# MCU_ESP32_S3.net
KiCad netlist of a schematic drawn in Altium Designer
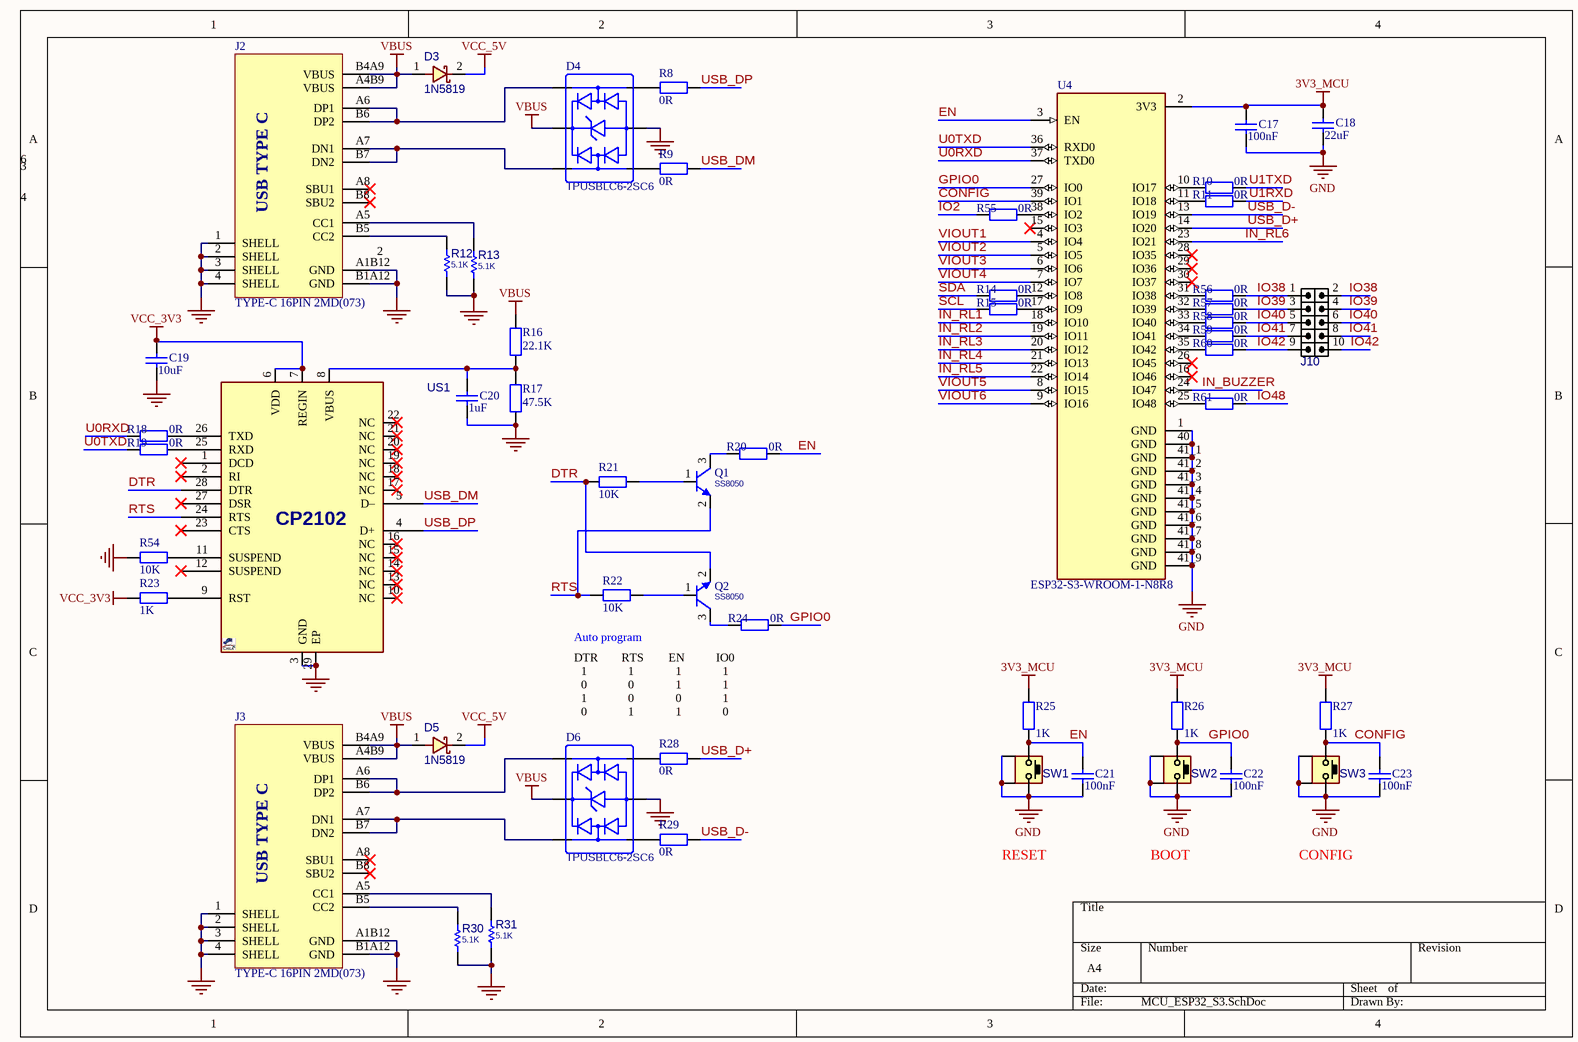
[diagram p0: MCU_ESP32_S3.SchDoc]

(export (version "E")
  (design (tool "Eeschema 10.0.6"))
  (components
    (comp (ref "C17")
      (value "100nF_0603_1%")
      (footprint "tu 0603")
      (description "Capacitor, Ceramic, 50V")
      (fields (field (name "MA_HANG") "100nF"))
      (libsource (lib "THU VIEN SCH") (part "Tu 0603 470pF 50V 10%"))
    )
    (comp (ref "C18")
      (value "22uF_0603_1%")
      (footprint "tu 0603")
      (description "Capacitor, Ceramic, 50V")
      (fields (field (name "MA_HANG") "22uF"))
      (libsource (lib "THU VIEN SCH") (part "Tu 0603 470pF 50V 10%"))
    )
    (comp (ref "C19")
      (value "10uF_0603_1%")
      (footprint "tu 0603")
      (description "Capacitor, Ceramic, 50V")
      (fields (field (name "MA_HANG") "10uF"))
      (libsource (lib "THU VIEN SCH") (part "Tu 0603 470pF 50V 10%"))
    )
    (comp (ref "C20")
      (value "1uF_0603_1%")
      (footprint "tu 0603")
      (description "Capacitor, Ceramic, 50V")
      (fields (field (name "MA_HANG") "1uF"))
      (libsource (lib "THU VIEN SCH") (part "Tu 0603 470pF 50V 10%"))
    )
    (comp (ref "C21")
      (value "100nF_0603_1%")
      (footprint "tu 0603")
      (description "Capacitor, Ceramic, 50V")
      (fields (field (name "MA_HANG") "100nF"))
      (libsource (lib "THU VIEN SCH") (part "Tu 0603 470pF 50V 10%"))
    )
    (comp (ref "C22")
      (value "100nF_0603_1%")
      (footprint "tu 0603")
      (description "Capacitor, Ceramic, 50V")
      (fields (field (name "MA_HANG") "100nF"))
      (libsource (lib "THU VIEN SCH") (part "Tu 0603 470pF 50V 10%"))
    )
    (comp (ref "C23")
      (value "100nF_0603_1%")
      (footprint "tu 0603")
      (description "Capacitor, Ceramic, 50V")
      (fields (field (name "MA_HANG") "100nF"))
      (libsource (lib "THU VIEN SCH") (part "Tu 0603 470pF 50V 10%"))
    )
    (comp (ref "D3")
      (value "1N5819")
      (footprint "D_SOD123W")
      (description "DIODE, SCHOTTKY, 40V, 1A")
      (fields (field (name "MANF") "DIODES") (field (name "MANF_P#") "1N5819HW-7-F"))
      (libsource (lib "AH_Library") (part "DIODE_SMD_SCHOTTKY_1N5819"))
    )
    (comp (ref "D4")
      (value "TPUSBLC6-2SC6")
      (footprint "SOT-23-6_L2.9-W1.6-P0.95-LS2.8-BR")
      (description "ESD ROHS SOT23-6 DIODES")
      (fields (field (name "LCSC PART NUMBER") "C558442") (field (name "MANUFACTURER") "TECH PUBLIC"))
      (libsource (lib "ESP32 S3 Gateway") (part "ESD_TPUSBLC6-2SC6"))
    )
    (comp (ref "D5")
      (value "1N5819")
      (footprint "D_SOD123W")
      (description "DIODE, SCHOTTKY, 40V, 1A")
      (fields (field (name "MANF") "DIODES") (field (name "MANF_P#") "1N5819HW-7-F"))
      (libsource (lib "AH_Library") (part "DIODE_SMD_SCHOTTKY_1N5819"))
    )
    (comp (ref "D6")
      (value "TPUSBLC6-2SC6")
      (footprint "SOT-23-6_L2.9-W1.6-P0.95-LS2.8-BR")
      (description "ESD ROHS SOT23-6 DIODES")
      (fields (field (name "LCSC PART NUMBER") "C558442") (field (name "MANUFACTURER") "TECH PUBLIC"))
      (libsource (lib "ESP32 S3 Gateway") (part "ESD_TPUSBLC6-2SC6"))
    )
    (comp (ref "J2")
      (value "TYPE-C 16PIN 2MD(073)")
      (footprint "USB-C-SMD_TYPE-C16PIN")
      (description "5A 1 Surface Mount 16 Female -25℃~+85℃ Type-C SMD USB Connectors ROHS")
      (fields
        (field (name "MANUFACTURER") "SHOU HAN")
        (field (name "MANUFACTURER PART NUMBER") "TYPE-C16PIN")
      )
      (libsource (lib "ESP32 S3 Gateway") (part "TYPE-C 16PIN 2MD(073)"))
    )
    (comp (ref "J3")
      (value "TYPE-C 16PIN 2MD(073)")
      (footprint "USB-C-SMD_TYPE-C16PIN")
      (description "5A 1 Surface Mount 16 Female -25℃~+85℃ Type-C SMD USB Connectors ROHS")
      (fields
        (field (name "MANUFACTURER") "SHOU HAN")
        (field (name "MANUFACTURER PART NUMBER") "TYPE-C16PIN")
      )
      (libsource (lib "ESP32 S3 Gateway") (part "TYPE-C 16PIN 2MD(073)"))
    )
    (comp (ref "J10")
      (value "HDRMINI_2X5")
      (footprint "HDRMINI_M_2X5")
      (description "CONN, HEADER, Male, pitch: 1.27mm, 10POS")
      (libsource (lib "AH_Library") (part "HDRMINI_M_2X5"))
    )
    (comp (ref "Q1")
      (value "SS8050")
      (footprint "SOT23_3")
      (description "BJT, NPN, 25v, 1.5A, SMD, SOT23")
      (fields (field (name "MANF_P#") "MMBT8050") (field (name "MANF") "GALAXY"))
      (libsource (lib "AH_Library") (part "NPN_MMBT8050_SOT23"))
    )
    (comp (ref "Q2")
      (value "SS8050")
      (footprint "SOT23_3")
      (description "BJT, NPN, 25v, 1.5A, SMD, SOT23")
      (fields (field (name "MANF_P#") "MMBT8050") (field (name "MANF") "GALAXY"))
      (libsource (lib "AH_Library") (part "NPN_MMBT8050_SOT23"))
    )
    (comp (ref "R8")
      (value "0R_0603_1%")
      (footprint "tro smd 0603")
      (description "RES SMD 0603")
      (fields (field (name "MA_HANG") "0R"))
      (libsource (lib "THU VIEN SCH") (part "Tro 0603 5% 10k"))
    )
    (comp (ref "R9")
      (value "0R_0603_1%")
      (footprint "tro smd 0603")
      (description "RES SMD 0603")
      (fields (field (name "MA_HANG") "0R"))
      (libsource (lib "THU VIEN SCH") (part "Tro 0603 5% 10k"))
    )
    (comp (ref "R10")
      (value "0R_0603_1%")
      (footprint "tro smd 0603")
      (description "RES SMD 0603")
      (fields (field (name "MA_HANG") "0R"))
      (libsource (lib "THU VIEN SCH") (part "Tro 0603 5% 10k"))
    )
    (comp (ref "R11")
      (value "0R_0603_1%")
      (footprint "tro smd 0603")
      (description "RES SMD 0603")
      (fields (field (name "MA_HANG") "0R"))
      (libsource (lib "THU VIEN SCH") (part "Tro 0603 5% 10k"))
    )
    (comp (ref "R12")
      (value "5.1K")
      (footprint "R0603")
      (description "RESISTOR, SMD")
      (fields (field (name "Comment") "5K1_0603_1%"))
      (libsource (lib "AH_Library") (part "RES_SMD_0603"))
    )
    (comp (ref "R13")
      (value "5.1K")
      (footprint "R0603")
      (description "RESISTOR, SMD")
      (fields (field (name "Comment") "5K1_0603_1%"))
      (libsource (lib "AH_Library") (part "RES_SMD_0603"))
    )
    (comp (ref "R14")
      (value "0R_0603_1%")
      (footprint "tro smd 0603")
      (description "RES SMD 0603")
      (fields (field (name "MA_HANG") "0R"))
      (libsource (lib "THU VIEN SCH") (part "Tro 0603 5% 10k"))
    )
    (comp (ref "R15")
      (value "0R_0603_1%")
      (footprint "tro smd 0603")
      (description "RES SMD 0603")
      (fields (field (name "MA_HANG") "0R"))
      (libsource (lib "THU VIEN SCH") (part "Tro 0603 5% 10k"))
    )
    (comp (ref "R16")
      (value "22.1K_0603_1%")
      (footprint "tro smd 0603")
      (description "RES SMD 0603")
      (fields (field (name "MA_HANG") "22.1K"))
      (libsource (lib "THU VIEN SCH") (part "Tro 0603 5% 10k"))
    )
    (comp (ref "R17")
      (value "47.5K_0603_1%")
      (footprint "tro smd 0603")
      (description "RES SMD 0603")
      (fields (field (name "MA_HANG") "47.5K"))
      (libsource (lib "THU VIEN SCH") (part "Tro 0603 5% 10k"))
    )
    (comp (ref "R18")
      (value "0R_0603_1%")
      (footprint "tro smd 0603")
      (description "RES SMD 0603")
      (fields (field (name "MA_HANG") "0R"))
      (libsource (lib "THU VIEN SCH") (part "Tro 0603 5% 10k"))
    )
    (comp (ref "R19")
      (value "0R_0603_1%")
      (footprint "tro smd 0603")
      (description "RES SMD 0603")
      (fields (field (name "MA_HANG") "0R"))
      (libsource (lib "THU VIEN SCH") (part "Tro 0603 5% 10k"))
    )
    (comp (ref "R20")
      (value "0R_0603_1%")
      (footprint "tro smd 0603")
      (description "RES SMD 0603")
      (fields (field (name "MA_HANG") "0R"))
      (libsource (lib "THU VIEN SCH") (part "Tro 0603 5% 10k"))
    )
    (comp (ref "R21")
      (value "10K_0603_1%")
      (footprint "tro smd 0603")
      (description "RES SMD 0603")
      (fields (field (name "MA_HANG") "10K"))
      (libsource (lib "THU VIEN SCH") (part "Tro 0603 5% 10k"))
    )
    (comp (ref "R22")
      (value "10K_0603_1%")
      (footprint "tro smd 0603")
      (description "RES SMD 0603")
      (fields (field (name "MA_HANG") "10K"))
      (libsource (lib "THU VIEN SCH") (part "Tro 0603 5% 10k"))
    )
    (comp (ref "R23")
      (value "1K_0603_1%")
      (footprint "tro smd 0603")
      (description "RES SMD 0603")
      (fields (field (name "MA_HANG") "1K"))
      (libsource (lib "THU VIEN SCH") (part "Tro 0603 5% 10k"))
    )
    (comp (ref "R24")
      (value "0R_0603_1%")
      (footprint "tro smd 0603")
      (description "RES SMD 0603")
      (fields (field (name "MA_HANG") "0R"))
      (libsource (lib "THU VIEN SCH") (part "Tro 0603 5% 10k"))
    )
    (comp (ref "R25")
      (value "1K_0603_1%")
      (footprint "tro smd 0603")
      (description "RES SMD 0603")
      (fields (field (name "MA_HANG") "1K"))
      (libsource (lib "THU VIEN SCH") (part "Tro 0603 5% 10k"))
    )
    (comp (ref "R26")
      (value "1K_0603_1%")
      (footprint "tro smd 0603")
      (description "RES SMD 0603")
      (fields (field (name "MA_HANG") "1K"))
      (libsource (lib "THU VIEN SCH") (part "Tro 0603 5% 10k"))
    )
    (comp (ref "R27")
      (value "1K_0603_1%")
      (footprint "tro smd 0603")
      (description "RES SMD 0603")
      (fields (field (name "MA_HANG") "1K"))
      (libsource (lib "THU VIEN SCH") (part "Tro 0603 5% 10k"))
    )
    (comp (ref "R28")
      (value "0R_0603_1%")
      (footprint "tro smd 0603")
      (description "RES SMD 0603")
      (fields (field (name "MA_HANG") "0R"))
      (libsource (lib "THU VIEN SCH") (part "Tro 0603 5% 10k"))
    )
    (comp (ref "R29")
      (value "0R_0603_1%")
      (footprint "tro smd 0603")
      (description "RES SMD 0603")
      (fields (field (name "MA_HANG") "0R"))
      (libsource (lib "THU VIEN SCH") (part "Tro 0603 5% 10k"))
    )
    (comp (ref "R30")
      (value "5.1K")
      (footprint "R0603")
      (description "RESISTOR, SMD")
      (fields (field (name "Comment") "5K1_0603_1%"))
      (libsource (lib "AH_Library") (part "RES_SMD_0603"))
    )
    (comp (ref "R31")
      (value "5.1K")
      (footprint "R0603")
      (description "RESISTOR, SMD")
      (fields (field (name "Comment") "5K1_0603_1%"))
      (libsource (lib "AH_Library") (part "RES_SMD_0603"))
    )
    (comp (ref "R54")
      (value "10K_0603_1%")
      (footprint "tro smd 0603")
      (description "RES SMD 0603")
      (fields (field (name "MA_HANG") "10K"))
      (libsource (lib "THU VIEN SCH") (part "Tro 0603 5% 10k"))
    )
    (comp (ref "R55")
      (value "0R_0603_1%")
      (footprint "tro smd 0603")
      (description "RES SMD 0603")
      (fields (field (name "MA_HANG") "0R"))
      (libsource (lib "THU VIEN SCH") (part "Tro 0603 5% 10k"))
    )
    (comp (ref "R56")
      (value "0R_0603_1%")
      (footprint "tro smd 0603")
      (description "RES SMD 0603")
      (fields (field (name "MA_HANG") "0R"))
      (libsource (lib "THU VIEN SCH") (part "Tro 0603 5% 10k"))
    )
    (comp (ref "R57")
      (value "0R_0603_1%")
      (footprint "tro smd 0603")
      (description "RES SMD 0603")
      (fields (field (name "MA_HANG") "0R"))
      (libsource (lib "THU VIEN SCH") (part "Tro 0603 5% 10k"))
    )
    (comp (ref "R58")
      (value "0R_0603_1%")
      (footprint "tro smd 0603")
      (description "RES SMD 0603")
      (fields (field (name "MA_HANG") "0R"))
      (libsource (lib "THU VIEN SCH") (part "Tro 0603 5% 10k"))
    )
    (comp (ref "R59")
      (value "0R_0603_1%")
      (footprint "tro smd 0603")
      (description "RES SMD 0603")
      (fields (field (name "MA_HANG") "0R"))
      (libsource (lib "THU VIEN SCH") (part "Tro 0603 5% 10k"))
    )
    (comp (ref "R60")
      (value "0R_0603_1%")
      (footprint "tro smd 0603")
      (description "RES SMD 0603")
      (fields (field (name "MA_HANG") "0R"))
      (libsource (lib "THU VIEN SCH") (part "Tro 0603 5% 10k"))
    )
    (comp (ref "R61")
      (value "0R_0603_1%")
      (footprint "tro smd 0603")
      (description "RES SMD 0603")
      (fields (field (name "MA_HANG") "0R"))
      (libsource (lib "THU VIEN SCH") (part "Tro 0603 5% 10k"))
    )
    (comp (ref "SW1")
      (value "PUSHBUTTON")
      (footprint "SWPBT_SPST_R_6X6X10")
      (description "SWITCH, PUSH BUTTON, TACTILE, THD, SPST, RIGHT")
      (libsource (lib "AH_Library") (part "SWPBT_SPST_R_6X6X10"))
    )
    (comp (ref "SW2")
      (value "PUSHBUTTON")
      (footprint "SWPBT_SPST_R_6X6X10")
      (description "SWITCH, PUSH BUTTON, TACTILE, THD, SPST, RIGHT")
      (libsource (lib "AH_Library") (part "SWPBT_SPST_R_6X6X10"))
    )
    (comp (ref "SW3")
      (value "PUSHBUTTON")
      (footprint "SWPBT_SPST_R_6X6X10")
      (description "SWITCH, PUSH BUTTON, TACTILE, THD, SPST, RIGHT")
      (libsource (lib "AH_Library") (part "SWPBT_SPST_R_6X6X10"))
    )
    (comp (ref "U4")
      (value "ESP32-S3-WROOM-1-N8R8")
      (footprint "XCVR_ESP32S3WROOM1N8R8")
      (description "Bluetooth, WiFi 802.11b/g/n, Bluetooth v5.0 Transceiver Module 2.4GHz PCB Trace Surface Mount")
      (fields (field (name "MF") "Espressif Systems"))
      (libsource (lib "ESP32-S3-WROOM-1-N8R8") (part "ESP32-S3-WROOM-1-N8R8"))
    )
    (comp (ref "US1")
      (value "CP2102_QFN28")
      (footprint "QFN50_28T")
      (description "USB-UART BRIDGE")
      (fields (field (name "MANF") "SILICON LABS") (field (name "MANF_1") "MANF"))
      (libsource (lib "AH_Library") (part "CP2102_QFN28"))
    )
  )
  (nets
    (net (code "1") (name "/CONFIG") (class "Default")
      (node (ref "C23") (pin "1") (pinfunction "1_1") (pintype "passive"))
      (node (ref "R27") (pin "1") (pinfunction "1_1") (pintype "passive"))
      (node (ref "SW3") (pin "1") (pinfunction "1_1") (pintype "passive"))
      (node (ref "U4") (pin "39") (pinfunction "IO1_39") (pintype "bidirectional"))
    )
    (net (code "2") (name "/DTR") (class "Default")
      (node (ref "Q2") (pin "2") (pinfunction "E_2") (pintype "passive"))
      (node (ref "R21") (pin "2") (pinfunction "2_2") (pintype "passive"))
      (node (ref "US1") (pin "28") (pinfunction "DTR_28") (pintype "passive"))
    )
    (net (code "3") (name "/EN") (class "Default")
      (node (ref "C21") (pin "1") (pinfunction "1_1") (pintype "passive"))
      (node (ref "R20") (pin "2") (pinfunction "2_2") (pintype "passive"))
      (node (ref "R25") (pin "1") (pinfunction "1_1") (pintype "passive"))
      (node (ref "SW1") (pin "1") (pinfunction "1_1") (pintype "passive"))
      (node (ref "U4") (pin "3") (pinfunction "EN_3") (pintype "input"))
    )
    (net (code "4") (name "/GPIO0") (class "Default")
      (node (ref "C22") (pin "1") (pinfunction "1_1") (pintype "passive"))
      (node (ref "R24") (pin "2") (pinfunction "2_2") (pintype "passive"))
      (node (ref "R26") (pin "1") (pinfunction "1_1") (pintype "passive"))
      (node (ref "SW2") (pin "1") (pinfunction "1_1") (pintype "passive"))
      (node (ref "U4") (pin "27") (pinfunction "IO0_27") (pintype "bidirectional"))
    )
    (net (code "5") (name "/IN_BUZZER") (class "Default")
      (node (ref "U4") (pin "24") (pinfunction "IO47_24") (pintype "bidirectional"))
    )
    (net (code "6") (name "/IN_RL1") (class "Default")
      (node (ref "U4") (pin "18") (pinfunction "IO10_18") (pintype "bidirectional"))
    )
    (net (code "7") (name "/IN_RL2") (class "Default")
      (node (ref "U4") (pin "19") (pinfunction "IO11_19") (pintype "bidirectional"))
    )
    (net (code "8") (name "/IN_RL3") (class "Default")
      (node (ref "U4") (pin "20") (pinfunction "IO12_20") (pintype "bidirectional"))
    )
    (net (code "9") (name "/IN_RL4") (class "Default")
      (node (ref "U4") (pin "21") (pinfunction "IO13_21") (pintype "bidirectional"))
    )
    (net (code "10") (name "/IN_RL5") (class "Default")
      (node (ref "U4") (pin "22") (pinfunction "IO14_22") (pintype "bidirectional"))
    )
    (net (code "11") (name "/IN_RL6") (class "Default")
      (node (ref "U4") (pin "23") (pinfunction "IO21_23") (pintype "bidirectional"))
    )
    (net (code "12") (name "/IO2") (class "Default")
      (node (ref "R55") (pin "1") (pinfunction "1_1") (pintype "passive"))
    )
    (net (code "13") (name "/IO38") (class "Default")
      (node (ref "J10") (pin "1") (pinfunction "1_1") (pintype "passive"))
      (node (ref "J10") (pin "2") (pinfunction "2_2") (pintype "passive"))
      (node (ref "R56") (pin "2") (pinfunction "2_2") (pintype "passive"))
    )
    (net (code "14") (name "/IO39") (class "Default")
      (node (ref "J10") (pin "3") (pinfunction "3_3") (pintype "passive"))
      (node (ref "J10") (pin "4") (pinfunction "4_4") (pintype "passive"))
      (node (ref "R57") (pin "2") (pinfunction "2_2") (pintype "passive"))
    )
    (net (code "15") (name "/IO40") (class "Default")
      (node (ref "J10") (pin "5") (pinfunction "5_5") (pintype "passive"))
      (node (ref "J10") (pin "6") (pinfunction "6_6") (pintype "passive"))
      (node (ref "R58") (pin "2") (pinfunction "2_2") (pintype "passive"))
    )
    (net (code "16") (name "/IO41") (class "Default")
      (node (ref "J10") (pin "7") (pinfunction "7_7") (pintype "passive"))
      (node (ref "J10") (pin "8") (pinfunction "8_8") (pintype "passive"))
      (node (ref "R59") (pin "2") (pinfunction "2_2") (pintype "passive"))
    )
    (net (code "17") (name "/IO42") (class "Default")
      (node (ref "J10") (pin "10") (pinfunction "10_10") (pintype "passive"))
      (node (ref "J10") (pin "9") (pinfunction "9_9") (pintype "passive"))
      (node (ref "R60") (pin "2") (pinfunction "2_2") (pintype "passive"))
    )
    (net (code "18") (name "/IO48") (class "Default")
      (node (ref "R61") (pin "2") (pinfunction "2_2") (pintype "passive"))
    )
    (net (code "19") (name "/RTS") (class "Default")
      (node (ref "Q1") (pin "2") (pinfunction "E_2") (pintype "passive"))
      (node (ref "R22") (pin "2") (pinfunction "2_2") (pintype "passive"))
      (node (ref "US1") (pin "24") (pinfunction "RTS_24") (pintype "passive"))
    )
    (net (code "20") (name "/SCL") (class "Default")
      (node (ref "R15") (pin "1") (pinfunction "1_1") (pintype "passive"))
    )
    (net (code "21") (name "/SDA") (class "Default")
      (node (ref "R14") (pin "1") (pinfunction "1_1") (pintype "passive"))
    )
    (net (code "22") (name "/U0RXD") (class "Default")
      (node (ref "R18") (pin "1") (pinfunction "1_1") (pintype "passive"))
      (node (ref "U4") (pin "37") (pinfunction "TXD0_37") (pintype "bidirectional"))
    )
    (net (code "23") (name "/U0TXD") (class "Default")
      (node (ref "R19") (pin "1") (pinfunction "1_1") (pintype "passive"))
      (node (ref "U4") (pin "36") (pinfunction "RXD0_36") (pintype "bidirectional"))
    )
    (net (code "24") (name "/U1RXD") (class "Default")
      (node (ref "R11") (pin "2") (pinfunction "2_2") (pintype "passive"))
    )
    (net (code "25") (name "/U1TXD") (class "Default")
      (node (ref "R10") (pin "2") (pinfunction "2_2") (pintype "passive"))
    )
    (net (code "26") (name "/USB_D+") (class "Default")
      (node (ref "R28") (pin "2") (pinfunction "2_2") (pintype "passive"))
      (node (ref "U4") (pin "14") (pinfunction "IO20_14") (pintype "bidirectional"))
    )
    (net (code "27") (name "/USB_D-") (class "Default")
      (node (ref "R29") (pin "2") (pinfunction "2_2") (pintype "passive"))
      (node (ref "U4") (pin "13") (pinfunction "IO19_13") (pintype "bidirectional"))
    )
    (net (code "28") (name "/USB_DM") (class "Default")
      (node (ref "R9") (pin "2") (pinfunction "2_2") (pintype "passive"))
      (node (ref "US1") (pin "5") (pinfunction "D–_5") (pintype "passive"))
    )
    (net (code "29") (name "/USB_DP") (class "Default")
      (node (ref "R8") (pin "2") (pinfunction "2_2") (pintype "passive"))
      (node (ref "US1") (pin "4") (pinfunction "D+_4") (pintype "passive"))
    )
    (net (code "30") (name "/VIOUT1") (class "Default")
      (node (ref "U4") (pin "4") (pinfunction "IO4_4") (pintype "bidirectional"))
    )
    (net (code "31") (name "/VIOUT2") (class "Default")
      (node (ref "U4") (pin "5") (pinfunction "IO5_5") (pintype "bidirectional"))
    )
    (net (code "32") (name "/VIOUT3") (class "Default")
      (node (ref "U4") (pin "6") (pinfunction "IO6_6") (pintype "bidirectional"))
    )
    (net (code "33") (name "/VIOUT4") (class "Default")
      (node (ref "U4") (pin "7") (pinfunction "IO7_7") (pintype "bidirectional"))
    )
    (net (code "34") (name "/VIOUT5") (class "Default")
      (node (ref "U4") (pin "8") (pinfunction "IO15_8") (pintype "bidirectional"))
    )
    (net (code "35") (name "/VIOUT6") (class "Default")
      (node (ref "U4") (pin "9") (pinfunction "IO16_9") (pintype "bidirectional"))
    )
    (net (code "36") (name "3V3_MCU") (class "Default")
      (node (ref "C17") (pin "1") (pinfunction "1_1") (pintype "passive"))
      (node (ref "C18") (pin "1") (pinfunction "1_1") (pintype "passive"))
      (node (ref "R25") (pin "2") (pinfunction "2_2") (pintype "passive"))
      (node (ref "R26") (pin "2") (pinfunction "2_2") (pintype "passive"))
      (node (ref "R27") (pin "2") (pinfunction "2_2") (pintype "passive"))
      (node (ref "U4") (pin "2") (pinfunction "3V3_2") (pintype "power_in"))
    )
    (net (code "37") (name "GND") (class "Default")
      (node (ref "C17") (pin "2") (pinfunction "2_2") (pintype "passive"))
      (node (ref "C18") (pin "2") (pinfunction "2_2") (pintype "passive"))
      (node (ref "C19") (pin "2") (pinfunction "2_2") (pintype "passive"))
      (node (ref "C20") (pin "2") (pinfunction "2_2") (pintype "passive"))
      (node (ref "C21") (pin "2") (pinfunction "2_2") (pintype "passive"))
      (node (ref "C22") (pin "2") (pinfunction "2_2") (pintype "passive"))
      (node (ref "C23") (pin "2") (pinfunction "2_2") (pintype "passive"))
      (node (ref "D4") (pin "2") (pinfunction "GND_2") (pintype "passive"))
      (node (ref "D6") (pin "2") (pinfunction "GND_2") (pintype "passive"))
      (node (ref "J2") (pin "1") (pinfunction "SHELL_1") (pintype "passive"))
      (node (ref "J2") (pin "2") (pinfunction "SHELL_2") (pintype "passive"))
      (node (ref "J2") (pin "3") (pinfunction "SHELL_3") (pintype "passive"))
      (node (ref "J2") (pin "4") (pinfunction "SHELL_4") (pintype "passive"))
      (node (ref "J2") (pin "A1B12") (pinfunction "GND_A1B12") (pintype "passive"))
      (node (ref "J2") (pin "B1A12") (pinfunction "GND_B1A12") (pintype "passive"))
      (node (ref "J3") (pin "1") (pinfunction "SHELL_1") (pintype "passive"))
      (node (ref "J3") (pin "2") (pinfunction "SHELL_2") (pintype "passive"))
      (node (ref "J3") (pin "3") (pinfunction "SHELL_3") (pintype "passive"))
      (node (ref "J3") (pin "4") (pinfunction "SHELL_4") (pintype "passive"))
      (node (ref "J3") (pin "A1B12") (pinfunction "GND_A1B12") (pintype "passive"))
      (node (ref "J3") (pin "B1A12") (pinfunction "GND_B1A12") (pintype "passive"))
      (node (ref "R12") (pin "2") (pinfunction "2_2") (pintype "passive"))
      (node (ref "R13") (pin "2") (pinfunction "2_2") (pintype "passive"))
      (node (ref "R17") (pin "2") (pinfunction "2_2") (pintype "passive"))
      (node (ref "R30") (pin "2") (pinfunction "2_2") (pintype "passive"))
      (node (ref "R31") (pin "2") (pinfunction "2_2") (pintype "passive"))
      (node (ref "R54") (pin "2") (pinfunction "2_2") (pintype "passive"))
      (node (ref "SW1") (pin "2") (pinfunction "2_2") (pintype "passive"))
      (node (ref "SW1") (pin "MH1") (pinfunction "MH1_MH1") (pintype "passive"))
      (node (ref "SW1") (pin "MH2") (pinfunction "MH2_MH2") (pintype "passive"))
      (node (ref "SW2") (pin "2") (pinfunction "2_2") (pintype "passive"))
      (node (ref "SW2") (pin "MH1") (pinfunction "MH1_MH1") (pintype "passive"))
      (node (ref "SW2") (pin "MH2") (pinfunction "MH2_MH2") (pintype "passive"))
      (node (ref "SW3") (pin "2") (pinfunction "2_2") (pintype "passive"))
      (node (ref "SW3") (pin "MH1") (pinfunction "MH1_MH1") (pintype "passive"))
      (node (ref "SW3") (pin "MH2") (pinfunction "MH2_MH2") (pintype "passive"))
      (node (ref "U4") (pin "1") (pinfunction "GND_1") (pintype "power_in"))
      (node (ref "U4") (pin "40") (pinfunction "GND_40") (pintype "power_in"))
      (node (ref "U4") (pin "41_1") (pinfunction "GND_41_1") (pintype "power_in"))
      (node (ref "U4") (pin "41_2") (pinfunction "GND_41_2") (pintype "power_in"))
      (node (ref "U4") (pin "41_3") (pinfunction "GND_41_3") (pintype "power_in"))
      (node (ref "U4") (pin "41_4") (pinfunction "GND_41_4") (pintype "power_in"))
      (node (ref "U4") (pin "41_5") (pinfunction "GND_41_5") (pintype "power_in"))
      (node (ref "U4") (pin "41_6") (pinfunction "GND_41_6") (pintype "power_in"))
      (node (ref "U4") (pin "41_7") (pinfunction "GND_41_7") (pintype "power_in"))
      (node (ref "U4") (pin "41_8") (pinfunction "GND_41_8") (pintype "power_in"))
      (node (ref "U4") (pin "41_9") (pinfunction "GND_41_9") (pintype "power_in"))
      (node (ref "US1") (pin "29") (pinfunction "EP_29") (pintype "passive"))
      (node (ref "US1") (pin "3") (pinfunction "GND_3") (pintype "passive"))
    )
    (net (code "38") (name "Net-(D4-I{slash}O1-Pad1)") (class "Default")
      (node (ref "D4") (pin "1") (pinfunction "I/O1_1") (pintype "passive"))
      (node (ref "R8") (pin "1") (pinfunction "1_1") (pintype "passive"))
    )
    (net (code "39") (name "Net-(D4-I{slash}O2-Pad3)") (class "Default")
      (node (ref "D4") (pin "3") (pinfunction "I/O2_3") (pintype "passive"))
      (node (ref "R9") (pin "1") (pinfunction "1_1") (pintype "passive"))
    )
    (net (code "40") (name "Net-(D6-I{slash}O1-Pad1)") (class "Default")
      (node (ref "D6") (pin "1") (pinfunction "I/O1_1") (pintype "passive"))
      (node (ref "R28") (pin "1") (pinfunction "1_1") (pintype "passive"))
    )
    (net (code "41") (name "Net-(D6-I{slash}O2-Pad3)") (class "Default")
      (node (ref "D6") (pin "3") (pinfunction "I/O2_3") (pintype "passive"))
      (node (ref "R29") (pin "1") (pinfunction "1_1") (pintype "passive"))
    )
    (net (code "42") (name "Net-(J2-CC1)") (class "Default")
      (node (ref "J2") (pin "A5") (pinfunction "CC1_A5") (pintype "passive"))
      (node (ref "R13") (pin "1") (pinfunction "1_1") (pintype "passive"))
    )
    (net (code "43") (name "Net-(J2-CC2)") (class "Default")
      (node (ref "J2") (pin "B5") (pinfunction "CC2_B5") (pintype "passive"))
      (node (ref "R12") (pin "1") (pinfunction "1_1") (pintype "passive"))
    )
    (net (code "44") (name "Net-(J2-DN1)") (class "Default")
      (node (ref "D4") (pin "4") (pinfunction "I/O2_4") (pintype "passive"))
      (node (ref "J2") (pin "A7") (pinfunction "DN1_A7") (pintype "passive"))
      (node (ref "J2") (pin "B7") (pinfunction "DN2_B7") (pintype "passive"))
    )
    (net (code "45") (name "Net-(J2-DP1)") (class "Default")
      (node (ref "D4") (pin "6") (pinfunction "I/O1_6") (pintype "passive"))
      (node (ref "J2") (pin "A6") (pinfunction "DP1_A6") (pintype "passive"))
      (node (ref "J2") (pin "B6") (pinfunction "DP2_B6") (pintype "passive"))
    )
    (net (code "46") (name "Net-(J3-CC1)") (class "Default")
      (node (ref "J3") (pin "A5") (pinfunction "CC1_A5") (pintype "passive"))
      (node (ref "R31") (pin "1") (pinfunction "1_1") (pintype "passive"))
    )
    (net (code "47") (name "Net-(J3-CC2)") (class "Default")
      (node (ref "J3") (pin "B5") (pinfunction "CC2_B5") (pintype "passive"))
      (node (ref "R30") (pin "1") (pinfunction "1_1") (pintype "passive"))
    )
    (net (code "48") (name "Net-(J3-DN1)") (class "Default")
      (node (ref "D6") (pin "4") (pinfunction "I/O2_4") (pintype "passive"))
      (node (ref "J3") (pin "A7") (pinfunction "DN1_A7") (pintype "passive"))
      (node (ref "J3") (pin "B7") (pinfunction "DN2_B7") (pintype "passive"))
    )
    (net (code "49") (name "Net-(J3-DP1)") (class "Default")
      (node (ref "D6") (pin "6") (pinfunction "I/O1_6") (pintype "passive"))
      (node (ref "J3") (pin "A6") (pinfunction "DP1_A6") (pintype "passive"))
      (node (ref "J3") (pin "B6") (pinfunction "DP2_B6") (pintype "passive"))
    )
    (net (code "50") (name "Net-(Q1-B)") (class "Default")
      (node (ref "Q1") (pin "1") (pinfunction "B_1") (pintype "passive"))
      (node (ref "R21") (pin "1") (pinfunction "1_1") (pintype "passive"))
    )
    (net (code "51") (name "Net-(Q1-C)") (class "Default")
      (node (ref "Q1") (pin "3") (pinfunction "C_3") (pintype "passive"))
      (node (ref "R20") (pin "1") (pinfunction "1_1") (pintype "passive"))
    )
    (net (code "52") (name "Net-(Q2-B)") (class "Default")
      (node (ref "Q2") (pin "1") (pinfunction "B_1") (pintype "passive"))
      (node (ref "R22") (pin "1") (pinfunction "1_1") (pintype "passive"))
    )
    (net (code "53") (name "Net-(Q2-C)") (class "Default")
      (node (ref "Q2") (pin "3") (pinfunction "C_3") (pintype "passive"))
      (node (ref "R24") (pin "1") (pinfunction "1_1") (pintype "passive"))
    )
    (net (code "54") (name "Net-(R54-Pad1)") (class "Default")
      (node (ref "R54") (pin "1") (pinfunction "1_1") (pintype "passive"))
      (node (ref "US1") (pin "11") (pinfunction "SUSPEND_11") (pintype "passive"))
    )
    (net (code "55") (name "Net-(U4-IO2)") (class "Default")
      (node (ref "R55") (pin "2") (pinfunction "2_2") (pintype "passive"))
      (node (ref "U4") (pin "38") (pinfunction "IO2_38") (pintype "bidirectional"))
    )
    (net (code "56") (name "Net-(U4-IO8)") (class "Default")
      (node (ref "R14") (pin "2") (pinfunction "2_2") (pintype "passive"))
      (node (ref "U4") (pin "12") (pinfunction "IO8_12") (pintype "bidirectional"))
    )
    (net (code "57") (name "Net-(U4-IO9)") (class "Default")
      (node (ref "R15") (pin "2") (pinfunction "2_2") (pintype "passive"))
      (node (ref "U4") (pin "17") (pinfunction "IO9_17") (pintype "bidirectional"))
    )
    (net (code "58") (name "Net-(U4-IO17)") (class "Default")
      (node (ref "R10") (pin "1") (pinfunction "1_1") (pintype "passive"))
      (node (ref "U4") (pin "10") (pinfunction "IO17_10") (pintype "bidirectional"))
    )
    (net (code "59") (name "Net-(U4-IO18)") (class "Default")
      (node (ref "R11") (pin "1") (pinfunction "1_1") (pintype "passive"))
      (node (ref "U4") (pin "11") (pinfunction "IO18_11") (pintype "bidirectional"))
    )
    (net (code "60") (name "Net-(U4-IO38)") (class "Default")
      (node (ref "R56") (pin "1") (pinfunction "1_1") (pintype "passive"))
      (node (ref "U4") (pin "31") (pinfunction "IO38_31") (pintype "bidirectional"))
    )
    (net (code "61") (name "Net-(U4-IO39)") (class "Default")
      (node (ref "R57") (pin "1") (pinfunction "1_1") (pintype "passive"))
      (node (ref "U4") (pin "32") (pinfunction "IO39_32") (pintype "bidirectional"))
    )
    (net (code "62") (name "Net-(U4-IO40)") (class "Default")
      (node (ref "R58") (pin "1") (pinfunction "1_1") (pintype "passive"))
      (node (ref "U4") (pin "33") (pinfunction "IO40_33") (pintype "bidirectional"))
    )
    (net (code "63") (name "Net-(U4-IO41)") (class "Default")
      (node (ref "R59") (pin "1") (pinfunction "1_1") (pintype "passive"))
      (node (ref "U4") (pin "34") (pinfunction "IO41_34") (pintype "bidirectional"))
    )
    (net (code "64") (name "Net-(U4-IO42)") (class "Default")
      (node (ref "R60") (pin "1") (pinfunction "1_1") (pintype "passive"))
      (node (ref "U4") (pin "35") (pinfunction "IO42_35") (pintype "bidirectional"))
    )
    (net (code "65") (name "Net-(U4-IO48)") (class "Default")
      (node (ref "R61") (pin "1") (pinfunction "1_1") (pintype "passive"))
      (node (ref "U4") (pin "25") (pinfunction "IO48_25") (pintype "bidirectional"))
    )
    (net (code "66") (name "Net-(US1-RST)") (class "Default")
      (node (ref "R23") (pin "2") (pinfunction "2_2") (pintype "passive"))
      (node (ref "US1") (pin "9") (pinfunction "RST_9") (pintype "passive"))
    )
    (net (code "67") (name "Net-(US1-RXD)") (class "Default")
      (node (ref "R19") (pin "2") (pinfunction "2_2") (pintype "passive"))
      (node (ref "US1") (pin "25") (pinfunction "RXD_25") (pintype "passive"))
    )
    (net (code "68") (name "Net-(US1-TXD)") (class "Default")
      (node (ref "R18") (pin "2") (pinfunction "2_2") (pintype "passive"))
      (node (ref "US1") (pin "26") (pinfunction "TXD_26") (pintype "passive"))
    )
    (net (code "69") (name "Net-(US1-VBUS)") (class "Default")
      (node (ref "C20") (pin "1") (pinfunction "1_1") (pintype "passive"))
      (node (ref "R16") (pin "2") (pinfunction "2_2") (pintype "passive"))
      (node (ref "R17") (pin "1") (pinfunction "1_1") (pintype "passive"))
      (node (ref "US1") (pin "8") (pinfunction "VBUS_8") (pintype "passive"))
    )
    (net (code "70") (name "VBUS") (class "Default")
      (node (ref "D3") (pin "1") (pinfunction "1_1") (pintype "passive"))
      (node (ref "D4") (pin "5") (pinfunction "VBUS_5") (pintype "passive"))
      (node (ref "D5") (pin "1") (pinfunction "1_1") (pintype "passive"))
      (node (ref "D6") (pin "5") (pinfunction "VBUS_5") (pintype "passive"))
      (node (ref "J2") (pin "A4B9") (pinfunction "VBUS_A4B9") (pintype "passive"))
      (node (ref "J2") (pin "B4A9") (pinfunction "VBUS_B4A9") (pintype "passive"))
      (node (ref "J3") (pin "A4B9") (pinfunction "VBUS_A4B9") (pintype "passive"))
      (node (ref "J3") (pin "B4A9") (pinfunction "VBUS_B4A9") (pintype "passive"))
      (node (ref "R16") (pin "1") (pinfunction "1_1") (pintype "passive"))
    )
    (net (code "71") (name "VCC_3V3") (class "Default")
      (node (ref "C19") (pin "1") (pinfunction "1_1") (pintype "passive"))
      (node (ref "R23") (pin "1") (pinfunction "1_1") (pintype "passive"))
      (node (ref "US1") (pin "6") (pinfunction "VDD_6") (pintype "passive"))
      (node (ref "US1") (pin "7") (pinfunction "REGIN_7") (pintype "passive"))
    )
    (net (code "72") (name "VCC_5V") (class "Default")
      (node (ref "D3") (pin "2") (pinfunction "2_2") (pintype "passive"))
      (node (ref "D5") (pin "2") (pinfunction "2_2") (pintype "passive"))
    )
    (net (code "73") (name "unconnected-(J2-SBU1-PadA8)") (class "Default")
      (node (ref "J2") (pin "A8") (pinfunction "SBU1_A8") (pintype "passive+no_connect"))
    )
    (net (code "74") (name "unconnected-(J2-SBU2-PadB8)") (class "Default")
      (node (ref "J2") (pin "B8") (pinfunction "SBU2_B8") (pintype "passive+no_connect"))
    )
    (net (code "75") (name "unconnected-(J3-SBU1-PadA8)") (class "Default")
      (node (ref "J3") (pin "A8") (pinfunction "SBU1_A8") (pintype "passive+no_connect"))
    )
    (net (code "76") (name "unconnected-(J3-SBU2-PadB8)") (class "Default")
      (node (ref "J3") (pin "B8") (pinfunction "SBU2_B8") (pintype "passive+no_connect"))
    )
    (net (code "77") (name "unconnected-(U4-IO3-Pad15)") (class "Default")
      (node (ref "U4") (pin "15") (pinfunction "IO3_15") (pintype "bidirectional+no_connect"))
    )
    (net (code "78") (name "unconnected-(U4-IO35-Pad28)") (class "Default")
      (node (ref "U4") (pin "28") (pinfunction "IO35_28") (pintype "bidirectional+no_connect"))
    )
    (net (code "79") (name "unconnected-(U4-IO36-Pad29)") (class "Default")
      (node (ref "U4") (pin "29") (pinfunction "IO36_29") (pintype "bidirectional+no_connect"))
    )
    (net (code "80") (name "unconnected-(U4-IO37-Pad30)") (class "Default")
      (node (ref "U4") (pin "30") (pinfunction "IO37_30") (pintype "bidirectional+no_connect"))
    )
    (net (code "81") (name "unconnected-(U4-IO45-Pad26)") (class "Default")
      (node (ref "U4") (pin "26") (pinfunction "IO45_26") (pintype "bidirectional+no_connect"))
    )
    (net (code "82") (name "unconnected-(U4-IO46-Pad16)") (class "Default")
      (node (ref "U4") (pin "16") (pinfunction "IO46_16") (pintype "bidirectional+no_connect"))
    )
    (net (code "83") (name "unconnected-(US1-CTS-Pad23)") (class "Default")
      (node (ref "US1") (pin "23") (pinfunction "CTS_23") (pintype "passive+no_connect"))
    )
    (net (code "84") (name "unconnected-(US1-DCD-Pad1)") (class "Default")
      (node (ref "US1") (pin "1") (pinfunction "DCD_1") (pintype "passive+no_connect"))
    )
    (net (code "85") (name "unconnected-(US1-DSR-Pad27)") (class "Default")
      (node (ref "US1") (pin "27") (pinfunction "DSR_27") (pintype "passive+no_connect"))
    )
    (net (code "86") (name "unconnected-(US1-NC-Pad10)") (class "Default")
      (node (ref "US1") (pin "10") (pinfunction "NC_10") (pintype "passive+no_connect"))
    )
    (net (code "87") (name "unconnected-(US1-NC-Pad13)") (class "Default")
      (node (ref "US1") (pin "13") (pinfunction "NC_13") (pintype "passive+no_connect"))
    )
    (net (code "88") (name "unconnected-(US1-NC-Pad14)") (class "Default")
      (node (ref "US1") (pin "14") (pinfunction "NC_14") (pintype "passive+no_connect"))
    )
    (net (code "89") (name "unconnected-(US1-NC-Pad15)") (class "Default")
      (node (ref "US1") (pin "15") (pinfunction "NC_15") (pintype "passive+no_connect"))
    )
    (net (code "90") (name "unconnected-(US1-NC-Pad16)") (class "Default")
      (node (ref "US1") (pin "16") (pinfunction "NC_16") (pintype "passive+no_connect"))
    )
    (net (code "91") (name "unconnected-(US1-NC-Pad17)") (class "Default")
      (node (ref "US1") (pin "17") (pinfunction "NC_17") (pintype "passive+no_connect"))
    )
    (net (code "92") (name "unconnected-(US1-NC-Pad18)") (class "Default")
      (node (ref "US1") (pin "18") (pinfunction "NC_18") (pintype "passive+no_connect"))
    )
    (net (code "93") (name "unconnected-(US1-NC-Pad19)") (class "Default")
      (node (ref "US1") (pin "19") (pinfunction "NC_19") (pintype "passive+no_connect"))
    )
    (net (code "94") (name "unconnected-(US1-NC-Pad20)") (class "Default")
      (node (ref "US1") (pin "20") (pinfunction "NC_20") (pintype "passive+no_connect"))
    )
    (net (code "95") (name "unconnected-(US1-NC-Pad21)") (class "Default")
      (node (ref "US1") (pin "21") (pinfunction "NC_21") (pintype "passive+no_connect"))
    )
    (net (code "96") (name "unconnected-(US1-NC-Pad22)") (class "Default")
      (node (ref "US1") (pin "22") (pinfunction "NC_22") (pintype "passive+no_connect"))
    )
    (net (code "97") (name "unconnected-(US1-RI-Pad2)") (class "Default")
      (node (ref "US1") (pin "2") (pinfunction "RI_2") (pintype "passive+no_connect"))
    )
    (net (code "98") (name "unconnected-(US1-SUSPEND-Pad12)") (class "Default")
      (node (ref "US1") (pin "12") (pinfunction "SUSPEND_12") (pintype "passive+no_connect"))
    )
  )
)
